# G848L.net
KiCad netlist of a schematic drawn in EAGLE
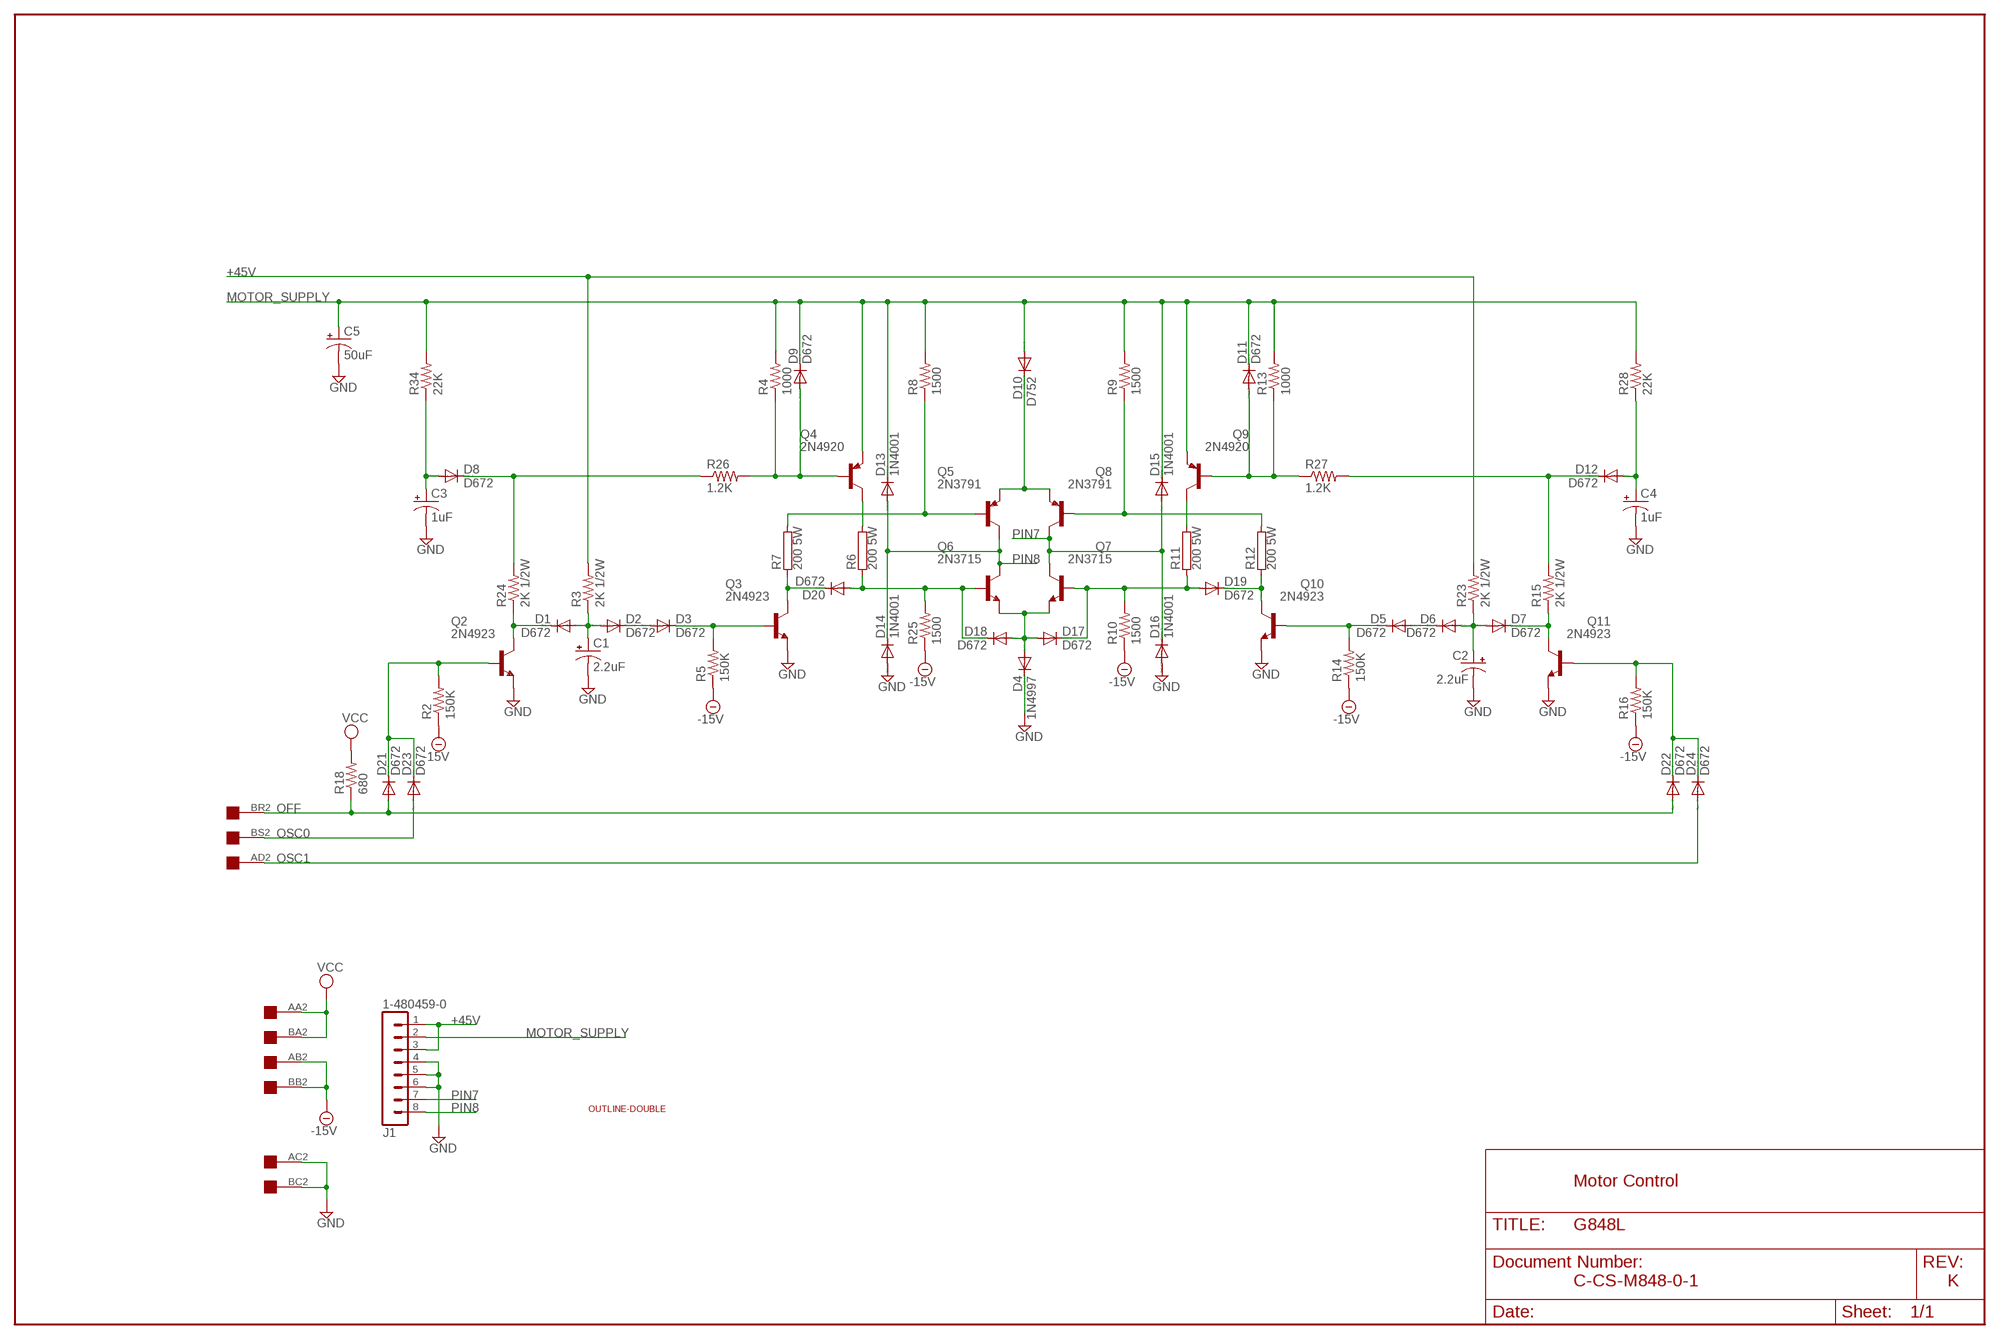
[diagram p0: schematic, sheet 1]

(export (version "E")
  (design (tool "Eeschema 10.0.6"))
  (components
    (comp (ref "C1")
      (value "2.2uF")
      (footprint "eagle-import:E15-5")
      (libsource (lib "eagle-import") (part "CPOL-USE15-5AXIAL"))
    )
    (comp (ref "C2")
      (value "2.2uF")
      (footprint "eagle-import:E15-5")
      (libsource (lib "eagle-import") (part "CPOL-USE15-5AXIAL"))
    )
    (comp (ref "C3")
      (value "1uF")
      (footprint "eagle-import:E15-5")
      (libsource (lib "eagle-import") (part "CPOL-USE15-5AXIAL"))
    )
    (comp (ref "C4")
      (value "1uF")
      (footprint "eagle-import:E15-5")
      (libsource (lib "eagle-import") (part "CPOL-USE15-5AXIAL"))
    )
    (comp (ref "C5")
      (value "50uF")
      (footprint "eagle-import:E30-10")
      (libsource (lib "eagle-import") (part "CPOL-USE30-10AXIAL"))
    )
    (comp (ref "D1")
      (value "D672")
      (footprint "eagle-import:DO35-10")
      (libsource (lib "eagle-import") (part "DIODE-DO35-10"))
    )
    (comp (ref "D2")
      (value "D672")
      (footprint "eagle-import:DO35-10")
      (libsource (lib "eagle-import") (part "DIODE-DO35-10"))
    )
    (comp (ref "D3")
      (value "D672")
      (footprint "eagle-import:DO35-10")
      (libsource (lib "eagle-import") (part "DIODE-DO35-10"))
    )
    (comp (ref "D4")
      (value "1N4997")
      (footprint "eagle-import:G4-12")
      (libsource (lib "eagle-import") (part "DIODE-G4-12"))
    )
    (comp (ref "D5")
      (value "D672")
      (footprint "eagle-import:DO35-10")
      (libsource (lib "eagle-import") (part "DIODE-DO35-10"))
    )
    (comp (ref "D6")
      (value "D672")
      (footprint "eagle-import:DO35-10")
      (libsource (lib "eagle-import") (part "DIODE-DO35-10"))
    )
    (comp (ref "D7")
      (value "D672")
      (footprint "eagle-import:DO35-10")
      (libsource (lib "eagle-import") (part "DIODE-DO35-10"))
    )
    (comp (ref "D8")
      (value "D672")
      (footprint "eagle-import:DO35-10")
      (libsource (lib "eagle-import") (part "DIODE-DO35-10"))
    )
    (comp (ref "D9")
      (value "D672")
      (footprint "eagle-import:DO35-10")
      (libsource (lib "eagle-import") (part "DIODE-DO35-10"))
    )
    (comp (ref "D10")
      (value "D752")
      (footprint "eagle-import:G4-12")
      (libsource (lib "eagle-import") (part "DIODE-G4-12"))
    )
    (comp (ref "D11")
      (value "D672")
      (footprint "eagle-import:DO35-10")
      (libsource (lib "eagle-import") (part "DIODE-DO35-10"))
    )
    (comp (ref "D12")
      (value "D672")
      (footprint "eagle-import:DO35-10")
      (libsource (lib "eagle-import") (part "DIODE-DO35-10"))
    )
    (comp (ref "D13")
      (value "1N4001")
      (footprint "eagle-import:DO41-10")
      (libsource (lib "eagle-import") (part "1N4004"))
    )
    (comp (ref "D14")
      (value "1N4001")
      (footprint "eagle-import:DO41-10")
      (libsource (lib "eagle-import") (part "1N4004"))
    )
    (comp (ref "D15")
      (value "1N4001")
      (footprint "eagle-import:DO41-10")
      (libsource (lib "eagle-import") (part "1N4004"))
    )
    (comp (ref "D16")
      (value "1N4001")
      (footprint "eagle-import:DO41-10")
      (libsource (lib "eagle-import") (part "1N4004"))
    )
    (comp (ref "D17")
      (value "D672")
      (footprint "eagle-import:DO35-10")
      (libsource (lib "eagle-import") (part "DIODE-DO35-10"))
    )
    (comp (ref "D18")
      (value "D672")
      (footprint "eagle-import:DO35-10")
      (libsource (lib "eagle-import") (part "DIODE-DO35-10"))
    )
    (comp (ref "D19")
      (value "D672")
      (footprint "eagle-import:DO35-10")
      (libsource (lib "eagle-import") (part "DIODE-DO35-10"))
    )
    (comp (ref "D20")
      (value "D672")
      (footprint "eagle-import:DO35-10")
      (libsource (lib "eagle-import") (part "DIODE-DO35-10"))
    )
    (comp (ref "D21")
      (value "D672")
      (footprint "eagle-import:DO35-10")
      (libsource (lib "eagle-import") (part "DIODE-DO35-10"))
    )
    (comp (ref "D22")
      (value "D672")
      (footprint "eagle-import:DO35-10")
      (libsource (lib "eagle-import") (part "DIODE-DO35-10"))
    )
    (comp (ref "D23")
      (value "D672")
      (footprint "eagle-import:DO35-10")
      (libsource (lib "eagle-import") (part "DIODE-DO35-10"))
    )
    (comp (ref "D24")
      (value "D672")
      (footprint "eagle-import:DO35-10")
      (libsource (lib "eagle-import") (part "DIODE-DO35-10"))
    )
    (comp (ref "J1")
      (value "1-480459-0")
      (footprint "eagle-import:1-480459-0")
      (libsource (lib "eagle-import") (part "1-480459-0"))
    )
    (comp (ref "Q2")
      (value "2N4923")
      (footprint "eagle-import:TO225AHH")
      (libsource (lib "eagle-import") (part "-NPN-TO225HH"))
    )
    (comp (ref "Q3")
      (value "2N4923")
      (footprint "eagle-import:TO225AHH")
      (libsource (lib "eagle-import") (part "-NPN-TO225HH"))
    )
    (comp (ref "Q4")
      (value "2N4920")
      (footprint "eagle-import:TO225AHH")
      (libsource (lib "eagle-import") (part "-PNP-TO225HH"))
    )
    (comp (ref "Q5")
      (value "2N3791")
      (footprint "eagle-import:TO3")
      (libsource (lib "eagle-import") (part "-PNP-TO3"))
    )
    (comp (ref "Q6")
      (value "2N3715")
      (footprint "eagle-import:TO3")
      (libsource (lib "eagle-import") (part "-NPN-TO3/"))
    )
    (comp (ref "Q7")
      (value "2N3715")
      (footprint "eagle-import:TO3")
      (libsource (lib "eagle-import") (part "-NPN-TO3/"))
    )
    (comp (ref "Q8")
      (value "2N3791")
      (footprint "eagle-import:TO3")
      (libsource (lib "eagle-import") (part "-PNP-TO3"))
    )
    (comp (ref "Q9")
      (value "2N4920")
      (footprint "eagle-import:TO225AHH")
      (libsource (lib "eagle-import") (part "-PNP-TO225HH"))
    )
    (comp (ref "Q10")
      (value "2N4923")
      (footprint "eagle-import:TO225AHH")
      (libsource (lib "eagle-import") (part "-NPN-TO225HH"))
    )
    (comp (ref "Q11")
      (value "2N4923")
      (footprint "eagle-import:TO225AHH")
      (libsource (lib "eagle-import") (part "-NPN-TO225HH"))
    )
    (comp (ref "R2")
      (value "150K")
      (footprint "eagle-import:0207_10")
      (libsource (lib "eagle-import") (part "R-US_0207/10"))
    )
    (comp (ref "R3")
      (value "2K 1/2W")
      (footprint "eagle-import:0411_15")
      (libsource (lib "eagle-import") (part "R-US_0411/15"))
    )
    (comp (ref "R4")
      (value "1000")
      (footprint "eagle-import:0207_10")
      (libsource (lib "eagle-import") (part "R-US_0207/10"))
    )
    (comp (ref "R5")
      (value "150K")
      (footprint "eagle-import:0207_10")
      (libsource (lib "eagle-import") (part "R-US_0207/10"))
    )
    (comp (ref "R6")
      (value "200 5W")
      (footprint "eagle-import:CA4090")
      (libsource (lib "eagle-import") (part "RCA4090"))
    )
    (comp (ref "R7")
      (value "200 5W")
      (footprint "eagle-import:CA4090")
      (libsource (lib "eagle-import") (part "RCA4090"))
    )
    (comp (ref "R8")
      (value "1500")
      (footprint "eagle-import:0207_10")
      (libsource (lib "eagle-import") (part "R-US_0207/10"))
    )
    (comp (ref "R9")
      (value "1500")
      (footprint "eagle-import:0207_10")
      (libsource (lib "eagle-import") (part "R-US_0207/10"))
    )
    (comp (ref "R10")
      (value "1500")
      (footprint "eagle-import:0207_10")
      (libsource (lib "eagle-import") (part "R-US_0207/10"))
    )
    (comp (ref "R11")
      (value "200 5W")
      (footprint "eagle-import:CA4090")
      (libsource (lib "eagle-import") (part "RCA4090"))
    )
    (comp (ref "R12")
      (value "200 5W")
      (footprint "eagle-import:CA4090")
      (libsource (lib "eagle-import") (part "RCA4090"))
    )
    (comp (ref "R13")
      (value "1000")
      (footprint "eagle-import:0207_10")
      (libsource (lib "eagle-import") (part "R-US_0207/10"))
    )
    (comp (ref "R14")
      (value "150K")
      (footprint "eagle-import:0207_10")
      (libsource (lib "eagle-import") (part "R-US_0207/10"))
    )
    (comp (ref "R15")
      (value "2K 1/2W")
      (footprint "eagle-import:0411_15")
      (libsource (lib "eagle-import") (part "R-US_0411/15"))
    )
    (comp (ref "R16")
      (value "150K")
      (footprint "eagle-import:0207_10")
      (libsource (lib "eagle-import") (part "R-US_0207/10"))
    )
    (comp (ref "R18")
      (value "680")
      (footprint "eagle-import:0207_10")
      (libsource (lib "eagle-import") (part "R-US_0207/10"))
    )
    (comp (ref "R23")
      (value "2K 1/2W")
      (footprint "eagle-import:0411_15")
      (libsource (lib "eagle-import") (part "R-US_0411/15"))
    )
    (comp (ref "R24")
      (value "2K 1/2W")
      (footprint "eagle-import:0411_15")
      (libsource (lib "eagle-import") (part "R-US_0411/15"))
    )
    (comp (ref "R25")
      (value "1500")
      (footprint "eagle-import:0207_10")
      (libsource (lib "eagle-import") (part "R-US_0207/10"))
    )
    (comp (ref "R26")
      (value "1.2K")
      (footprint "eagle-import:0207_10")
      (libsource (lib "eagle-import") (part "R-US_0207/10"))
    )
    (comp (ref "R27")
      (value "1.2K")
      (footprint "eagle-import:0207_10")
      (libsource (lib "eagle-import") (part "R-US_0207/10"))
    )
    (comp (ref "R28")
      (value "22K")
      (footprint "eagle-import:0207_10")
      (libsource (lib "eagle-import") (part "R-US_0207/10"))
    )
    (comp (ref "R34")
      (value "22K")
      (footprint "eagle-import:0207_10")
      (libsource (lib "eagle-import") (part "R-US_0207/10"))
    )
    (comp (ref "U$1")
      (value "DOUBLE")
      (footprint "eagle-import:EDGE-CON4")
      (libsource (lib "eagle-import") (part "DOUBLE"))
    )
    (comp (ref "U$2")
      (value "OUTLINE-DOUBLE")
      (footprint "eagle-import:DOUBLE")
      (libsource (lib "eagle-import") (part "OUTLINE-DOUBLE"))
    )
  )
  (nets
    (net (code "1") (name "-15V") (class "Default")
      (node (ref "R10") (pin "1") (pinfunction "1_1") (pintype "passive"))
      (node (ref "R14") (pin "1") (pinfunction "1_1") (pintype "passive"))
      (node (ref "R16") (pin "1") (pinfunction "1_1") (pintype "passive"))
      (node (ref "R2") (pin "1") (pinfunction "1_1") (pintype "passive"))
      (node (ref "R25") (pin "1") (pinfunction "1_1") (pintype "passive"))
      (node (ref "R5") (pin "1") (pinfunction "1_1") (pintype "passive"))
      (node (ref "U$1") (pin "AB2") (pinfunction "1_AB2") (pintype "bidirectional"))
      (node (ref "U$1") (pin "BB2") (pinfunction "1_BB2") (pintype "bidirectional"))
    )
    (net (code "2") (name "/+45V") (class "Default")
      (node (ref "J1") (pin "1") (pinfunction "1_1") (pintype "passive"))
      (node (ref "J1") (pin "3") (pinfunction "3_3") (pintype "passive"))
      (node (ref "R23") (pin "2") (pinfunction "2_2") (pintype "passive"))
      (node (ref "R3") (pin "2") (pinfunction "2_2") (pintype "passive"))
    )
    (net (code "3") (name "/MOTOR_SUPPLY") (class "Default")
      (node (ref "C5") (pin "+") (pinfunction "+_+") (pintype "passive"))
      (node (ref "D10") (pin "A") (pinfunction "A_A") (pintype "passive"))
      (node (ref "D11") (pin "C") (pinfunction "C_C") (pintype "passive"))
      (node (ref "D13") (pin "C") (pinfunction "C_C") (pintype "passive"))
      (node (ref "D15") (pin "C") (pinfunction "C_C") (pintype "passive"))
      (node (ref "D9") (pin "C") (pinfunction "C_C") (pintype "passive"))
      (node (ref "J1") (pin "2") (pinfunction "2_2") (pintype "passive"))
      (node (ref "Q4") (pin "1") (pinfunction "E_1") (pintype "passive"))
      (node (ref "Q9") (pin "1") (pinfunction "E_1") (pintype "passive"))
      (node (ref "R13") (pin "2") (pinfunction "2_2") (pintype "passive"))
      (node (ref "R28") (pin "2") (pinfunction "2_2") (pintype "passive"))
      (node (ref "R34") (pin "2") (pinfunction "2_2") (pintype "passive"))
      (node (ref "R4") (pin "2") (pinfunction "2_2") (pintype "passive"))
      (node (ref "R8") (pin "2") (pinfunction "2_2") (pintype "passive"))
      (node (ref "R9") (pin "2") (pinfunction "2_2") (pintype "passive"))
    )
    (net (code "4") (name "/OFF") (class "Default")
      (node (ref "D21") (pin "A") (pinfunction "A_A") (pintype "passive"))
      (node (ref "D22") (pin "A") (pinfunction "A_A") (pintype "passive"))
      (node (ref "R18") (pin "1") (pinfunction "1_1") (pintype "passive"))
      (node (ref "U$1") (pin "BR2") (pinfunction "1_BR2") (pintype "bidirectional"))
    )
    (net (code "5") (name "/OSC0") (class "Default")
      (node (ref "D23") (pin "A") (pinfunction "A_A") (pintype "passive"))
      (node (ref "U$1") (pin "BS2") (pinfunction "1_BS2") (pintype "bidirectional"))
    )
    (net (code "6") (name "/OSC1") (class "Default")
      (node (ref "D24") (pin "A") (pinfunction "A_A") (pintype "passive"))
      (node (ref "U$1") (pin "AD2") (pinfunction "1_AD2") (pintype "bidirectional"))
    )
    (net (code "7") (name "/PIN7") (class "Default")
      (node (ref "D15") (pin "A") (pinfunction "A_A") (pintype "passive"))
      (node (ref "D16") (pin "C") (pinfunction "C_C") (pintype "passive"))
      (node (ref "J1") (pin "7") (pinfunction "7_7") (pintype "passive"))
      (node (ref "Q7") (pin "C") (pinfunction "C_C") (pintype "passive"))
      (node (ref "Q7") (pin "C/") (pinfunction "C_C/") (pintype "passive"))
      (node (ref "Q8") (pin "C") (pinfunction "C_C") (pintype "passive"))
      (node (ref "Q8") (pin "C/") (pinfunction "C_C/") (pintype "passive"))
    )
    (net (code "8") (name "/PIN8") (class "Default")
      (node (ref "D13") (pin "A") (pinfunction "A_A") (pintype "passive"))
      (node (ref "D14") (pin "C") (pinfunction "C_C") (pintype "passive"))
      (node (ref "J1") (pin "8") (pinfunction "8_8") (pintype "passive"))
      (node (ref "Q5") (pin "C") (pinfunction "C_C") (pintype "passive"))
      (node (ref "Q5") (pin "C/") (pinfunction "C_C/") (pintype "passive"))
      (node (ref "Q6") (pin "C") (pinfunction "C_C") (pintype "passive"))
      (node (ref "Q6") (pin "C/") (pinfunction "C_C/") (pintype "passive"))
    )
    (net (code "9") (name "GND") (class "Default")
      (node (ref "C1") (pin "-") (pinfunction "-_-") (pintype "passive"))
      (node (ref "C2") (pin "-") (pinfunction "-_-") (pintype "passive"))
      (node (ref "C3") (pin "-") (pinfunction "-_-") (pintype "passive"))
      (node (ref "C4") (pin "-") (pinfunction "-_-") (pintype "passive"))
      (node (ref "C5") (pin "-") (pinfunction "-_-") (pintype "passive"))
      (node (ref "D14") (pin "A") (pinfunction "A_A") (pintype "passive"))
      (node (ref "D16") (pin "A") (pinfunction "A_A") (pintype "passive"))
      (node (ref "D4") (pin "C") (pinfunction "C_C") (pintype "passive"))
      (node (ref "J1") (pin "4") (pinfunction "4_4") (pintype "passive"))
      (node (ref "J1") (pin "5") (pinfunction "5_5") (pintype "passive"))
      (node (ref "J1") (pin "6") (pinfunction "6_6") (pintype "passive"))
      (node (ref "Q10") (pin "1") (pinfunction "E_1") (pintype "passive"))
      (node (ref "Q11") (pin "1") (pinfunction "E_1") (pintype "passive"))
      (node (ref "Q2") (pin "1") (pinfunction "E_1") (pintype "passive"))
      (node (ref "Q3") (pin "1") (pinfunction "E_1") (pintype "passive"))
      (node (ref "U$1") (pin "AC2") (pinfunction "1_AC2") (pintype "bidirectional"))
      (node (ref "U$1") (pin "BC2") (pinfunction "1_BC2") (pintype "bidirectional"))
    )
    (net (code "10") (name "Net-(C1-Pad+)") (class "Default")
      (node (ref "C1") (pin "+") (pinfunction "+_+") (pintype "passive"))
      (node (ref "D1") (pin "A") (pinfunction "A_A") (pintype "passive"))
      (node (ref "D2") (pin "A") (pinfunction "A_A") (pintype "passive"))
      (node (ref "R3") (pin "1") (pinfunction "1_1") (pintype "passive"))
    )
    (net (code "11") (name "Net-(C2-Pad+)") (class "Default")
      (node (ref "C2") (pin "+") (pinfunction "+_+") (pintype "passive"))
      (node (ref "D6") (pin "A") (pinfunction "A_A") (pintype "passive"))
      (node (ref "D7") (pin "A") (pinfunction "A_A") (pintype "passive"))
      (node (ref "R23") (pin "1") (pinfunction "1_1") (pintype "passive"))
    )
    (net (code "12") (name "Net-(C3-Pad+)") (class "Default")
      (node (ref "C3") (pin "+") (pinfunction "+_+") (pintype "passive"))
      (node (ref "D8") (pin "A") (pinfunction "A_A") (pintype "passive"))
      (node (ref "R34") (pin "1") (pinfunction "1_1") (pintype "passive"))
    )
    (net (code "13") (name "Net-(C4-Pad+)") (class "Default")
      (node (ref "C4") (pin "+") (pinfunction "+_+") (pintype "passive"))
      (node (ref "D12") (pin "A") (pinfunction "A_A") (pintype "passive"))
      (node (ref "R28") (pin "1") (pinfunction "1_1") (pintype "passive"))
    )
    (net (code "14") (name "Net-(D2-PadC)") (class "Default")
      (node (ref "D2") (pin "C") (pinfunction "C_C") (pintype "passive"))
      (node (ref "D3") (pin "A") (pinfunction "A_A") (pintype "passive"))
    )
    (net (code "15") (name "Net-(D5-PadA)") (class "Default")
      (node (ref "D5") (pin "A") (pinfunction "A_A") (pintype "passive"))
      (node (ref "D6") (pin "C") (pinfunction "C_C") (pintype "passive"))
    )
    (net (code "16") (name "Net-(D8-PadC)") (class "Default")
      (node (ref "D8") (pin "C") (pinfunction "C_C") (pintype "passive"))
      (node (ref "R24") (pin "2") (pinfunction "2_2") (pintype "passive"))
      (node (ref "R26") (pin "1") (pinfunction "1_1") (pintype "passive"))
    )
    (net (code "17") (name "Net-(D10-PadC)") (class "Default")
      (node (ref "D10") (pin "C") (pinfunction "C_C") (pintype "passive"))
      (node (ref "Q5") (pin "E") (pinfunction "E_E") (pintype "passive"))
      (node (ref "Q8") (pin "E") (pinfunction "E_E") (pintype "passive"))
    )
    (net (code "18") (name "Net-(D12-PadC)") (class "Default")
      (node (ref "D12") (pin "C") (pinfunction "C_C") (pintype "passive"))
      (node (ref "R15") (pin "2") (pinfunction "2_2") (pintype "passive"))
      (node (ref "R27") (pin "2") (pinfunction "2_2") (pintype "passive"))
    )
    (net (code "19") (name "Net-(D17-PadA)") (class "Default")
      (node (ref "D17") (pin "A") (pinfunction "A_A") (pintype "passive"))
      (node (ref "D18") (pin "A") (pinfunction "A_A") (pintype "passive"))
      (node (ref "D4") (pin "A") (pinfunction "A_A") (pintype "passive"))
      (node (ref "Q6") (pin "E") (pinfunction "E_E") (pintype "passive"))
      (node (ref "Q7") (pin "E") (pinfunction "E_E") (pintype "passive"))
    )
    (net (code "20") (name "Net-(D17-PadC)") (class "Default")
      (node (ref "D17") (pin "C") (pinfunction "C_C") (pintype "passive"))
      (node (ref "D19") (pin "A") (pinfunction "A_A") (pintype "passive"))
      (node (ref "Q7") (pin "B") (pinfunction "B_B") (pintype "passive"))
      (node (ref "R10") (pin "2") (pinfunction "2_2") (pintype "passive"))
      (node (ref "R11") (pin "1") (pinfunction "1_1") (pintype "passive"))
    )
    (net (code "21") (name "Net-(D18-PadC)") (class "Default")
      (node (ref "D18") (pin "C") (pinfunction "C_C") (pintype "passive"))
      (node (ref "D20") (pin "A") (pinfunction "A_A") (pintype "passive"))
      (node (ref "Q6") (pin "B") (pinfunction "B_B") (pintype "passive"))
      (node (ref "R25") (pin "2") (pinfunction "2_2") (pintype "passive"))
      (node (ref "R6") (pin "1") (pinfunction "1_1") (pintype "passive"))
    )
    (net (code "22") (name "Net-(Q2-B)") (class "Default")
      (node (ref "D21") (pin "C") (pinfunction "C_C") (pintype "passive"))
      (node (ref "D23") (pin "C") (pinfunction "C_C") (pintype "passive"))
      (node (ref "Q2") (pin "3") (pinfunction "B_3") (pintype "passive"))
      (node (ref "R2") (pin "2") (pinfunction "2_2") (pintype "passive"))
    )
    (net (code "23") (name "Net-(Q2-C)") (class "Default")
      (node (ref "D1") (pin "C") (pinfunction "C_C") (pintype "passive"))
      (node (ref "Q2") (pin "2") (pinfunction "C_2") (pintype "passive"))
      (node (ref "R24") (pin "1") (pinfunction "1_1") (pintype "passive"))
    )
    (net (code "24") (name "Net-(Q3-B)") (class "Default")
      (node (ref "D3") (pin "C") (pinfunction "C_C") (pintype "passive"))
      (node (ref "Q3") (pin "3") (pinfunction "B_3") (pintype "passive"))
      (node (ref "R5") (pin "2") (pinfunction "2_2") (pintype "passive"))
    )
    (net (code "25") (name "Net-(Q3-C)") (class "Default")
      (node (ref "D20") (pin "C") (pinfunction "C_C") (pintype "passive"))
      (node (ref "Q3") (pin "2") (pinfunction "C_2") (pintype "passive"))
      (node (ref "R7") (pin "1") (pinfunction "1_1") (pintype "passive"))
    )
    (net (code "26") (name "Net-(Q4-B)") (class "Default")
      (node (ref "D9") (pin "A") (pinfunction "A_A") (pintype "passive"))
      (node (ref "Q4") (pin "3") (pinfunction "B_3") (pintype "passive"))
      (node (ref "R26") (pin "2") (pinfunction "2_2") (pintype "passive"))
      (node (ref "R4") (pin "1") (pinfunction "1_1") (pintype "passive"))
    )
    (net (code "27") (name "Net-(Q4-C)") (class "Default")
      (node (ref "Q4") (pin "2") (pinfunction "C_2") (pintype "passive"))
      (node (ref "R6") (pin "2") (pinfunction "2_2") (pintype "passive"))
    )
    (net (code "28") (name "Net-(Q5-PadB)") (class "Default")
      (node (ref "Q5") (pin "B") (pinfunction "B_B") (pintype "passive"))
      (node (ref "R7") (pin "2") (pinfunction "2_2") (pintype "passive"))
      (node (ref "R8") (pin "1") (pinfunction "1_1") (pintype "passive"))
    )
    (net (code "29") (name "Net-(Q8-PadB)") (class "Default")
      (node (ref "Q8") (pin "B") (pinfunction "B_B") (pintype "passive"))
      (node (ref "R12") (pin "2") (pinfunction "2_2") (pintype "passive"))
      (node (ref "R9") (pin "1") (pinfunction "1_1") (pintype "passive"))
    )
    (net (code "30") (name "Net-(Q9-B)") (class "Default")
      (node (ref "D11") (pin "A") (pinfunction "A_A") (pintype "passive"))
      (node (ref "Q9") (pin "3") (pinfunction "B_3") (pintype "passive"))
      (node (ref "R13") (pin "1") (pinfunction "1_1") (pintype "passive"))
      (node (ref "R27") (pin "1") (pinfunction "1_1") (pintype "passive"))
    )
    (net (code "31") (name "Net-(Q9-C)") (class "Default")
      (node (ref "Q9") (pin "2") (pinfunction "C_2") (pintype "passive"))
      (node (ref "R11") (pin "2") (pinfunction "2_2") (pintype "passive"))
    )
    (net (code "32") (name "Net-(Q10-B)") (class "Default")
      (node (ref "D5") (pin "C") (pinfunction "C_C") (pintype "passive"))
      (node (ref "Q10") (pin "3") (pinfunction "B_3") (pintype "passive"))
      (node (ref "R14") (pin "2") (pinfunction "2_2") (pintype "passive"))
    )
    (net (code "33") (name "Net-(Q10-C)") (class "Default")
      (node (ref "D19") (pin "C") (pinfunction "C_C") (pintype "passive"))
      (node (ref "Q10") (pin "2") (pinfunction "C_2") (pintype "passive"))
      (node (ref "R12") (pin "1") (pinfunction "1_1") (pintype "passive"))
    )
    (net (code "34") (name "Net-(Q11-B)") (class "Default")
      (node (ref "D22") (pin "C") (pinfunction "C_C") (pintype "passive"))
      (node (ref "D24") (pin "C") (pinfunction "C_C") (pintype "passive"))
      (node (ref "Q11") (pin "3") (pinfunction "B_3") (pintype "passive"))
      (node (ref "R16") (pin "2") (pinfunction "2_2") (pintype "passive"))
    )
    (net (code "35") (name "Net-(Q11-C)") (class "Default")
      (node (ref "D7") (pin "C") (pinfunction "C_C") (pintype "passive"))
      (node (ref "Q11") (pin "2") (pinfunction "C_2") (pintype "passive"))
      (node (ref "R15") (pin "1") (pinfunction "1_1") (pintype "passive"))
    )
    (net (code "36") (name "VCC") (class "Default")
      (node (ref "R18") (pin "2") (pinfunction "2_2") (pintype "passive"))
      (node (ref "U$1") (pin "AA2") (pinfunction "1_AA2") (pintype "bidirectional"))
      (node (ref "U$1") (pin "BA2") (pinfunction "1_BA2") (pintype "bidirectional"))
    )
  )
)
